# RfUsbAdapter.net
KiCad netlist of a schematic drawn in Altium Designer
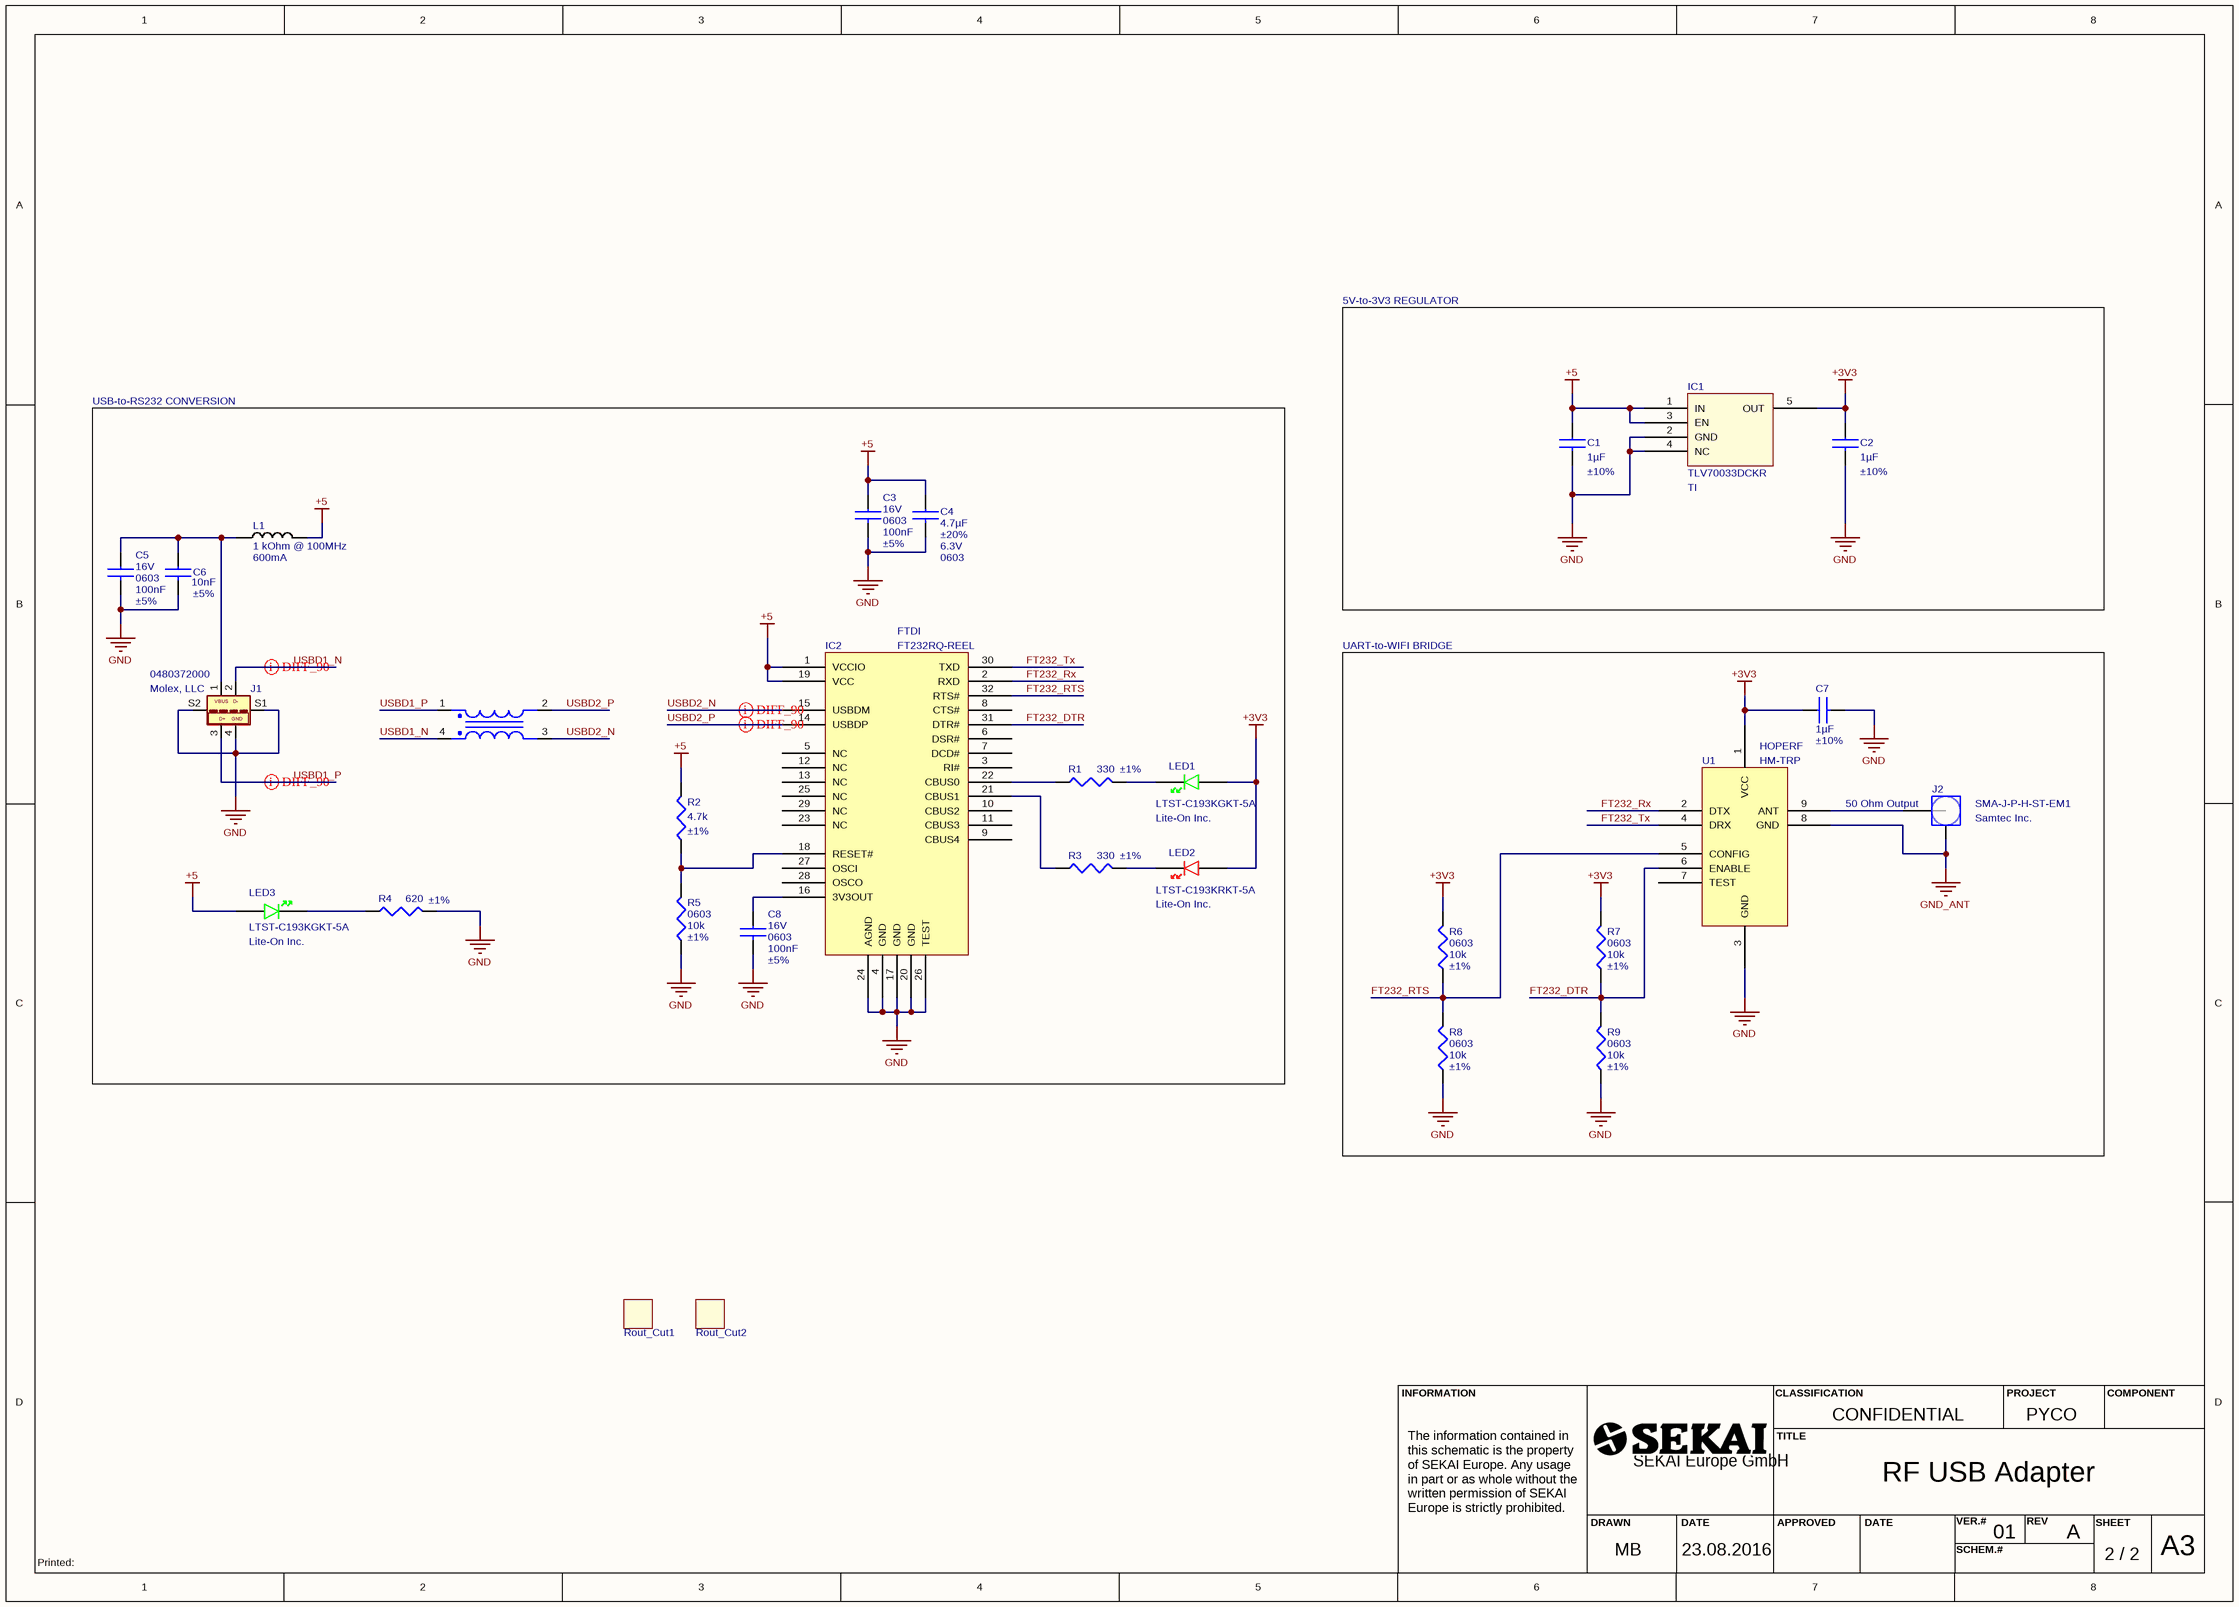
[diagram p0: RfUsbAdapter.SchDoc]

(export (version "E")
  (design (tool "Eeschema 10.0.6"))
  (components
    (comp (ref "C1")
      (value "GRM188R61C105KA93D")
      (footprint "C0603")
      (description "CAP CER 1UF 16V 10% X5R 0603")
      (fields
        (field (name "MANUFACTURER") "Murata Electronics North America")
        (field (name "CAPACITANCE") "1µF")
        (field (name "TOLERANCE") "±10%")
      )
      (libsource (lib "CAP") (part "GRM188R61C105KA93D"))
    )
    (comp (ref "C2")
      (value "GRM188R61C105KA93D")
      (footprint "C0603")
      (description "CAP CER 1UF 16V 10% X5R 0603")
      (fields
        (field (name "MANUFACTURER") "Murata Electronics North America")
        (field (name "CAPACITANCE") "1µF")
        (field (name "TOLERANCE") "±10%")
      )
      (libsource (lib "CAP") (part "GRM188R61C105KA93D"))
    )
    (comp (ref "C3")
      (value "C0603C104J4RACTU")
      (footprint "C0603")
      (description "100nF 16V 5% X7R 0603")
      (fields
        (field (name "MANUFACTURER") "Kemet")
        (field (name "SPANNUNG - NENNWERT") "16V")
        (field (name "GEHÄUSE / HÜLLE") "0603")
        (field (name "KAPAZITÄT") "100nF")
        (field (name "TOLERANZ") "±5%")
      )
      (libsource (lib "CAP") (part "C0603C104J4RACTU"))
    )
    (comp (ref "C4")
      (value "GRM188R60J475ME19D")
      (footprint "C0603")
      (description "CAP CER 4.7UF 6.3V X5R 0603")
      (fields
        (field (name "MANUFACTURER") "Murata Electronics North America")
        (field (name "CAPACITANCE") "4.7µF")
        (field (name "TOLERANCE") "±20%")
        (field (name "VOLTAGE - RATED") "6.3V")
        (field (name "PACKAGE / CASE") "0603")
      )
      (libsource (lib "CAP") (part "GRM188R60J475ME19D"))
    )
    (comp (ref "C5")
      (value "C0603C104J4RACTU")
      (footprint "C0603")
      (description "100nF 16V 5% X7R 0603")
      (fields
        (field (name "MANUFACTURER") "Kemet")
        (field (name "SPANNUNG - NENNWERT") "16V")
        (field (name "GEHÄUSE / HÜLLE") "0603")
        (field (name "KAPAZITÄT") "100nF")
        (field (name "TOLERANZ") "±5%")
      )
      (libsource (lib "CAP") (part "C0603C104J4RACTU"))
    )
    (comp (ref "C6")
      (value "GRM1857U1A103JA44D")
      (footprint "C0603")
      (description "CAP CER 10NF 10V 5% U2J 0603")
      (fields
        (field (name "MANUFACTURER") "Murata Electronics North America")
        (field (name "KAPAZITÄT") "10nF")
        (field (name "TOLERANZ") "±5%")
      )
      (libsource (lib "CAP") (part "GRM1857U1A103JA44D"))
    )
    (comp (ref "C7")
      (value "GRM188R61C105KA93D")
      (footprint "C0603")
      (description "CAP CER 1UF 16V 10% X5R 0603")
      (fields
        (field (name "MANUFACTURER") "Murata Electronics North America")
        (field (name "CAPACITANCE") "1µF")
        (field (name "TOLERANCE") "±10%")
      )
      (libsource (lib "CAP") (part "GRM188R61C105KA93D"))
    )
    (comp (ref "C8")
      (value "C0603C104J4RACTU")
      (footprint "C0603")
      (description "100nF 16V 5% X7R 0603")
      (fields
        (field (name "MANUFACTURER") "Kemet")
        (field (name "SPANNUNG - NENNWERT") "16V")
        (field (name "GEHÄUSE / HÜLLE") "0603")
        (field (name "KAPAZITÄT") "100nF")
        (field (name "TOLERANZ") "±5%")
      )
      (libsource (lib "CAP") (part "C0603C104J4RACTU"))
    )
    (comp (ref "IC1")
      (value "TLV70033DCKR")
      (footprint "SOT-353")
      (description "IC REG LDO 3.3V 0.2A SC70-5")
      (fields (field (name "MANUFACTURER") "TI"))
      (libsource (lib "LDO_TI") (part "TLV70033DCKR"))
    )
    (comp (ref "IC2")
      (value "FT232RQ-REEL")
      (footprint "QFN32-5x5")
      (description "IC USB FS SERIAL UART 32-QFN")
      (fields (field (name "MANUFACTURER") "FTDI"))
      (libsource (lib "USB_FTDI") (part "FT232RQ-REEL"))
    )
    (comp (ref "J1")
      (value "0480372000")
      (footprint "USB TYPE A 2.0")
      (description "CONN PLUG USB 4POS R/A SMD")
      (fields (field (name "MANUFACTURER") "Molex, LLC"))
      (libsource (lib "CON_Molex") (part "0480372000"))
    )
    (comp (ref "J2")
      (value "SMA-J-P-H-ST-EM1")
      (footprint "SMA-J-P-H-ST-EM1")
      (description "CONN SMA JACK 50 OHM EDGE MNT")
      (fields (field (name "MANUFACTURER") "Samtec Inc."))
      (libsource (lib "CON_Samtec") (part "SMA-J-P-H-ST-EM1"))
    )
    (comp (ref "L1")
      (value "FBMH1608HM102-T")
      (footprint "R0603")
      (description "FERRITE BEAD 1 KOHM 0603 1LN")
      (fields
        (field (name "MANUFACTURER") "Taiyo Yuden")
        (field (name "IMPEDANCE @ FREQUENCY") "1 kOhm @ 100MHz")
        (field (name "CURRENT RATING (MAX)") "600mA")
      )
      (libsource (lib "FB_Murata") (part "FBMH1608HM102-T"))
    )
    (comp (ref "L2")
      (value "DLW21SN121HQ2L")
      (footprint "IND_DLW21S_0805")
      (description "CHOKE COIL COMMON MODE 280MA SMD")
      (fields (field (name "MANUFACTURER") "Murata Electronics North America"))
      (libsource (lib "EMI_FIL_Murata") (part "DLW21SN121HQ2L"))
    )
    (comp (ref "LED1")
      (value "LTST-C193KGKT-5A")
      (footprint "LED0603-GREEN")
      (description "LED GREEN CLEAR 0603 SMD")
      (fields (field (name "MANUFACTURER") "Lite-On Inc."))
      (libsource (lib "LED_Standard") (part "LTST-C193KGKT-5A"))
    )
    (comp (ref "LED2")
      (value "LTST-C193KRKT-5A")
      (footprint "LED0603-RED")
      (description "LED RED CLEAR 0603 SMD")
      (fields (field (name "MANUFACTURER") "Lite-On Inc."))
      (libsource (lib "LED_Standard") (part "LTST-C193KRKT-5A"))
    )
    (comp (ref "LED3")
      (value "LTST-C193KGKT-5A")
      (footprint "LED0603-GREEN")
      (description "LED GREEN CLEAR 0603 SMD")
      (fields (field (name "MANUFACTURER") "Lite-On Inc."))
      (libsource (lib "LED_Standard") (part "LTST-C193KGKT-5A"))
    )
    (comp (ref "R1")
      (value "ERJ-3EKF3300V")
      (footprint "R0603")
      (description "RES SMD 330 OHM 1% 1/10W 0603")
      (fields
        (field (name "MANUFACTURER") "Panasonic Electronic Components")
        (field (name "RESISTANCE (OHMS)") "330")
        (field (name "TOLERANCE") "±1%")
      )
      (libsource (lib "RES") (part "ERJ-3EKF3300V"))
    )
    (comp (ref "R2")
      (value "ERJ-3EKF4701V")
      (footprint "R0603")
      (description "RES SMD 4.7K OHM 1% 1/10W 0603")
      (fields
        (field (name "MANUFACTURER") "Panasonic Electronic Components")
        (field (name "RESISTANCE (OHMS)") "4.7k")
        (field (name "TOLERANCE") "±1%")
      )
      (libsource (lib "RES") (part "ERJ-3EKF4701V"))
    )
    (comp (ref "R3")
      (value "ERJ-3EKF3300V")
      (footprint "R0603")
      (description "RES SMD 330 OHM 1% 1/10W 0603")
      (fields
        (field (name "MANUFACTURER") "Panasonic Electronic Components")
        (field (name "RESISTANCE (OHMS)") "330")
        (field (name "TOLERANCE") "±1%")
      )
      (libsource (lib "RES") (part "ERJ-3EKF3300V"))
    )
    (comp (ref "R4")
      (value "ERJ-3EKF6200V")
      (footprint "R0603")
      (description "620 OHM 1% 1/10W 0603")
      (fields
        (field (name "MANUFACTURER") "Panasonic Electronic Components")
        (field (name "RESISTANCE (OHMS)") "620")
        (field (name "TOLERANCE") "±1%")
      )
      (libsource (lib "RES") (part "ERJ-3EKF6200V"))
    )
    (comp (ref "R5")
      (value "ERJ-3EKF1002V")
      (footprint "R0603")
      (description "10K OHM 1% 1/10W 0603")
      (fields
        (field (name "MANUFACTURER") "Panasonic Electronic Components")
        (field (name "SUPPLIER DEVICE PACKAGE") "0603")
        (field (name "RESISTANCE (OHMS)") "10k")
        (field (name "TOLERANCE") "±1%")
      )
      (libsource (lib "RES") (part "ERJ-3EKF1002V"))
    )
    (comp (ref "R6")
      (value "ERJ-3EKF1002V")
      (footprint "R0603")
      (description "10K OHM 1% 1/10W 0603")
      (fields
        (field (name "MANUFACTURER") "Panasonic Electronic Components")
        (field (name "SUPPLIER DEVICE PACKAGE") "0603")
        (field (name "RESISTANCE (OHMS)") "10k")
        (field (name "TOLERANCE") "±1%")
      )
      (libsource (lib "RES") (part "ERJ-3EKF1002V"))
    )
    (comp (ref "R7")
      (value "ERJ-3EKF1002V")
      (footprint "R0603")
      (description "10K OHM 1% 1/10W 0603")
      (fields
        (field (name "MANUFACTURER") "Panasonic Electronic Components")
        (field (name "SUPPLIER DEVICE PACKAGE") "0603")
        (field (name "RESISTANCE (OHMS)") "10k")
        (field (name "TOLERANCE") "±1%")
      )
      (libsource (lib "RES") (part "ERJ-3EKF1002V"))
    )
    (comp (ref "R8")
      (value "ERJ-3EKF1002V")
      (footprint "R0603")
      (description "10K OHM 1% 1/10W 0603")
      (fields
        (field (name "MANUFACTURER") "Panasonic Electronic Components")
        (field (name "SUPPLIER DEVICE PACKAGE") "0603")
        (field (name "RESISTANCE (OHMS)") "10k")
        (field (name "TOLERANCE") "±1%")
      )
      (libsource (lib "RES") (part "ERJ-3EKF1002V"))
    )
    (comp (ref "R9")
      (value "ERJ-3EKF1002V")
      (footprint "R0603")
      (description "10K OHM 1% 1/10W 0603")
      (fields
        (field (name "MANUFACTURER") "Panasonic Electronic Components")
        (field (name "SUPPLIER DEVICE PACKAGE") "0603")
        (field (name "RESISTANCE (OHMS)") "10k")
        (field (name "TOLERANCE") "±1%")
      )
      (libsource (lib "RES") (part "ERJ-3EKF1002V"))
    )
    (comp (ref "Rout_Cut1")
      (value "Rout_Cut")
      (footprint "RoutCut")
      (description "1.6mm")
      (libsource (lib "Misc") (part "Rout_Cut"))
    )
    (comp (ref "Rout_Cut2")
      (value "Rout_Cut")
      (footprint "RoutCut")
      (description "1.6mm")
      (libsource (lib "Misc") (part "Rout_Cut"))
    )
    (comp (ref "U1")
      (value "HM-TRP")
      (footprint "HM-TRP")
      (fields (field (name "MANUFACTURER") "HOPERF"))
      (libsource (lib "RF_HOPERF") (part "HM-TRP"))
    )
  )
  (nets
    (net (code "1") (name "+3V3") (class "Default")
      (node (ref "C2") (pin "1") (pinfunction "1_1") (pintype "passive"))
      (node (ref "C7") (pin "1") (pinfunction "1_1") (pintype "passive"))
      (node (ref "IC1") (pin "5") (pinfunction "OUT_5") (pintype "passive"))
      (node (ref "LED1") (pin "1") (pinfunction "ANODE_1") (pintype "passive"))
      (node (ref "LED2") (pin "1") (pinfunction "ANODE_1") (pintype "passive"))
      (node (ref "R6") (pin "2") (pinfunction "2_2") (pintype "passive"))
      (node (ref "R7") (pin "2") (pinfunction "2_2") (pintype "passive"))
      (node (ref "U1") (pin "1") (pinfunction "VCC_1") (pintype "passive"))
    )
    (net (code "2") (name "+5") (class "Default")
      (node (ref "C1") (pin "1") (pinfunction "1_1") (pintype "passive"))
      (node (ref "C3") (pin "1") (pinfunction "1_1") (pintype "passive"))
      (node (ref "C4") (pin "1") (pinfunction "1_1") (pintype "passive"))
      (node (ref "IC1") (pin "1") (pinfunction "IN_1") (pintype "passive"))
      (node (ref "IC1") (pin "3") (pinfunction "EN_3") (pintype "passive"))
      (node (ref "IC2") (pin "1") (pinfunction "VCCIO_1") (pintype "passive"))
      (node (ref "IC2") (pin "19") (pinfunction "VCC_19") (pintype "passive"))
      (node (ref "L1") (pin "2") (pinfunction "2_2") (pintype "passive"))
      (node (ref "LED3") (pin "1") (pinfunction "ANODE_1") (pintype "passive"))
      (node (ref "R2") (pin "2") (pinfunction "2_2") (pintype "passive"))
    )
    (net (code "3") (name "/FT232_DTR") (class "Default")
      (node (ref "IC2") (pin "31") (pinfunction "DTR#_31") (pintype "passive"))
      (node (ref "R7") (pin "1") (pinfunction "1_1") (pintype "passive"))
      (node (ref "R9") (pin "2") (pinfunction "2_2") (pintype "passive"))
      (node (ref "U1") (pin "6") (pinfunction "ENABLE_6") (pintype "passive"))
    )
    (net (code "4") (name "/FT232_RTS") (class "Default")
      (node (ref "IC2") (pin "32") (pinfunction "RTS#_32") (pintype "passive"))
      (node (ref "R6") (pin "1") (pinfunction "1_1") (pintype "passive"))
      (node (ref "R8") (pin "2") (pinfunction "2_2") (pintype "passive"))
      (node (ref "U1") (pin "5") (pinfunction "CONFIG_5") (pintype "passive"))
    )
    (net (code "5") (name "/FT232_Rx") (class "Default")
      (node (ref "IC2") (pin "2") (pinfunction "RXD_2") (pintype "passive"))
      (node (ref "U1") (pin "2") (pinfunction "DTX_2") (pintype "passive"))
    )
    (net (code "6") (name "/FT232_Tx") (class "Default")
      (node (ref "IC2") (pin "30") (pinfunction "TXD_30") (pintype "passive"))
      (node (ref "U1") (pin "4") (pinfunction "DRX_4") (pintype "passive"))
    )
    (net (code "7") (name "/USBD1_N") (class "Default")
      (node (ref "J1") (pin "2") (pinfunction "D-_2") (pintype "passive"))
      (node (ref "L2") (pin "4") (pinfunction "4_4") (pintype "passive"))
    )
    (net (code "8") (name "/USBD1_P") (class "Default")
      (node (ref "J1") (pin "3") (pinfunction "D+_3") (pintype "passive"))
      (node (ref "L2") (pin "1") (pinfunction "1_1") (pintype "passive"))
    )
    (net (code "9") (name "/USBD2_N") (class "Default")
      (node (ref "IC2") (pin "15") (pinfunction "USBDM_15") (pintype "passive"))
      (node (ref "L2") (pin "3") (pinfunction "3_3") (pintype "passive"))
    )
    (net (code "10") (name "/USBD2_P") (class "Default")
      (node (ref "IC2") (pin "14") (pinfunction "USBDP_14") (pintype "passive"))
      (node (ref "L2") (pin "2") (pinfunction "2_2") (pintype "passive"))
    )
    (net (code "11") (name "GND") (class "Default")
      (node (ref "C1") (pin "2") (pinfunction "2_2") (pintype "passive"))
      (node (ref "C2") (pin "2") (pinfunction "2_2") (pintype "passive"))
      (node (ref "C3") (pin "2") (pinfunction "2_2") (pintype "passive"))
      (node (ref "C4") (pin "2") (pinfunction "2_2") (pintype "passive"))
      (node (ref "C5") (pin "2") (pinfunction "2_2") (pintype "passive"))
      (node (ref "C6") (pin "2") (pinfunction "2_2") (pintype "passive"))
      (node (ref "C7") (pin "2") (pinfunction "2_2") (pintype "passive"))
      (node (ref "C8") (pin "2") (pinfunction "2_2") (pintype "passive"))
      (node (ref "IC1") (pin "2") (pinfunction "GND_2") (pintype "passive"))
      (node (ref "IC1") (pin "4") (pinfunction "NC_4") (pintype "passive"))
      (node (ref "IC2") (pin "17") (pinfunction "GND_17") (pintype "passive"))
      (node (ref "IC2") (pin "20") (pinfunction "GND_20") (pintype "passive"))
      (node (ref "IC2") (pin "24") (pinfunction "AGND_24") (pintype "passive"))
      (node (ref "IC2") (pin "26") (pinfunction "TEST_26") (pintype "passive"))
      (node (ref "IC2") (pin "4") (pinfunction "GND_4") (pintype "passive"))
      (node (ref "J1") (pin "4") (pinfunction "GND_4") (pintype "passive"))
      (node (ref "J1") (pin "S1") (pinfunction "S1_S1") (pintype "passive"))
      (node (ref "J1") (pin "S2") (pinfunction "S2_S2") (pintype "passive"))
      (node (ref "R4") (pin "2") (pinfunction "2_2") (pintype "passive"))
      (node (ref "R5") (pin "1") (pinfunction "1_1") (pintype "passive"))
      (node (ref "R8") (pin "1") (pinfunction "1_1") (pintype "passive"))
      (node (ref "R9") (pin "1") (pinfunction "1_1") (pintype "passive"))
      (node (ref "U1") (pin "3") (pinfunction "GND_3") (pintype "passive"))
    )
    (net (code "12") (name "GND_ANT") (class "Default")
      (node (ref "J2") (pin "2") (pinfunction "2_2") (pintype "passive"))
      (node (ref "U1") (pin "8") (pinfunction "GND_8") (pintype "passive"))
    )
    (net (code "13") (name "Net-(IC2-3V3OUT)") (class "Default")
      (node (ref "C8") (pin "1") (pinfunction "1_1") (pintype "passive"))
      (node (ref "IC2") (pin "16") (pinfunction "3V3OUT_16") (pintype "passive"))
    )
    (net (code "14") (name "Net-(IC2-CBUS0)") (class "Default")
      (node (ref "IC2") (pin "22") (pinfunction "CBUS0_22") (pintype "passive"))
      (node (ref "R1") (pin "1") (pinfunction "1_1") (pintype "passive"))
    )
    (net (code "15") (name "Net-(IC2-CBUS1)") (class "Default")
      (node (ref "IC2") (pin "21") (pinfunction "CBUS1_21") (pintype "passive"))
      (node (ref "R3") (pin "1") (pinfunction "1_1") (pintype "passive"))
    )
    (net (code "16") (name "Net-(IC2-RESET#)") (class "Default")
      (node (ref "IC2") (pin "18") (pinfunction "RESET#_18") (pintype "passive"))
      (node (ref "R2") (pin "1") (pinfunction "1_1") (pintype "passive"))
      (node (ref "R5") (pin "2") (pinfunction "2_2") (pintype "passive"))
    )
    (net (code "17") (name "Net-(J1-VBUS)") (class "Default")
      (node (ref "C5") (pin "1") (pinfunction "1_1") (pintype "passive"))
      (node (ref "C6") (pin "1") (pinfunction "1_1") (pintype "passive"))
      (node (ref "J1") (pin "1") (pinfunction "VBUS_1") (pintype "passive"))
      (node (ref "L1") (pin "1") (pinfunction "1_1") (pintype "passive"))
    )
    (net (code "18") (name "Net-(LED1-CATHODE)") (class "Default")
      (node (ref "LED1") (pin "2") (pinfunction "CATHODE_2") (pintype "passive"))
      (node (ref "R1") (pin "2") (pinfunction "2_2") (pintype "passive"))
    )
    (net (code "19") (name "Net-(LED2-CATHODE)") (class "Default")
      (node (ref "LED2") (pin "2") (pinfunction "CATHODE_2") (pintype "passive"))
      (node (ref "R3") (pin "2") (pinfunction "2_2") (pintype "passive"))
    )
    (net (code "20") (name "Net-(LED3-CATHODE)") (class "Default")
      (node (ref "LED3") (pin "2") (pinfunction "CATHODE_2") (pintype "passive"))
      (node (ref "R4") (pin "1") (pinfunction "1_1") (pintype "passive"))
    )
    (net (code "21") (name "Net-(U1-ANT)") (class "Default")
      (node (ref "J2") (pin "1") (pinfunction "1_1") (pintype "passive"))
      (node (ref "U1") (pin "9") (pinfunction "ANT_9") (pintype "passive"))
    )
    (net (code "22") (name "unconnected-(IC2-CBUS2-Pad10)") (class "Default")
      (node (ref "IC2") (pin "10") (pinfunction "CBUS2_10") (pintype "passive"))
    )
    (net (code "23") (name "unconnected-(IC2-CBUS3-Pad11)") (class "Default")
      (node (ref "IC2") (pin "11") (pinfunction "CBUS3_11") (pintype "passive"))
    )
    (net (code "24") (name "unconnected-(IC2-CBUS4-Pad9)") (class "Default")
      (node (ref "IC2") (pin "9") (pinfunction "CBUS4_9") (pintype "passive"))
    )
    (net (code "25") (name "unconnected-(IC2-CTS#-Pad8)") (class "Default")
      (node (ref "IC2") (pin "8") (pinfunction "CTS#_8") (pintype "passive"))
    )
    (net (code "26") (name "unconnected-(IC2-DCD#-Pad7)") (class "Default")
      (node (ref "IC2") (pin "7") (pinfunction "DCD#_7") (pintype "passive"))
    )
    (net (code "27") (name "unconnected-(IC2-DSR#-Pad6)") (class "Default")
      (node (ref "IC2") (pin "6") (pinfunction "DSR#_6") (pintype "passive"))
    )
    (net (code "28") (name "unconnected-(IC2-NC-Pad5)") (class "Default")
      (node (ref "IC2") (pin "5") (pinfunction "NC_5") (pintype "passive"))
    )
    (net (code "29") (name "unconnected-(IC2-NC-Pad12)") (class "Default")
      (node (ref "IC2") (pin "12") (pinfunction "NC_12") (pintype "passive"))
    )
    (net (code "30") (name "unconnected-(IC2-NC-Pad13)") (class "Default")
      (node (ref "IC2") (pin "13") (pinfunction "NC_13") (pintype "passive"))
    )
    (net (code "31") (name "unconnected-(IC2-NC-Pad23)") (class "Default")
      (node (ref "IC2") (pin "23") (pinfunction "NC_23") (pintype "passive"))
    )
    (net (code "32") (name "unconnected-(IC2-NC-Pad25)") (class "Default")
      (node (ref "IC2") (pin "25") (pinfunction "NC_25") (pintype "passive"))
    )
    (net (code "33") (name "unconnected-(IC2-NC-Pad29)") (class "Default")
      (node (ref "IC2") (pin "29") (pinfunction "NC_29") (pintype "passive"))
    )
    (net (code "34") (name "unconnected-(IC2-OSCI-Pad27)") (class "Default")
      (node (ref "IC2") (pin "27") (pinfunction "OSCI_27") (pintype "passive"))
    )
    (net (code "35") (name "unconnected-(IC2-OSCO-Pad28)") (class "Default")
      (node (ref "IC2") (pin "28") (pinfunction "OSCO_28") (pintype "passive"))
    )
    (net (code "36") (name "unconnected-(IC2-RI#-Pad3)") (class "Default")
      (node (ref "IC2") (pin "3") (pinfunction "RI#_3") (pintype "passive"))
    )
    (net (code "37") (name "unconnected-(U1-TEST-Pad7)") (class "Default")
      (node (ref "U1") (pin "7") (pinfunction "TEST_7") (pintype "passive"))
    )
  )
)
